# LapTopBoard.net
KiCad netlist of a schematic drawn in Altium Designer
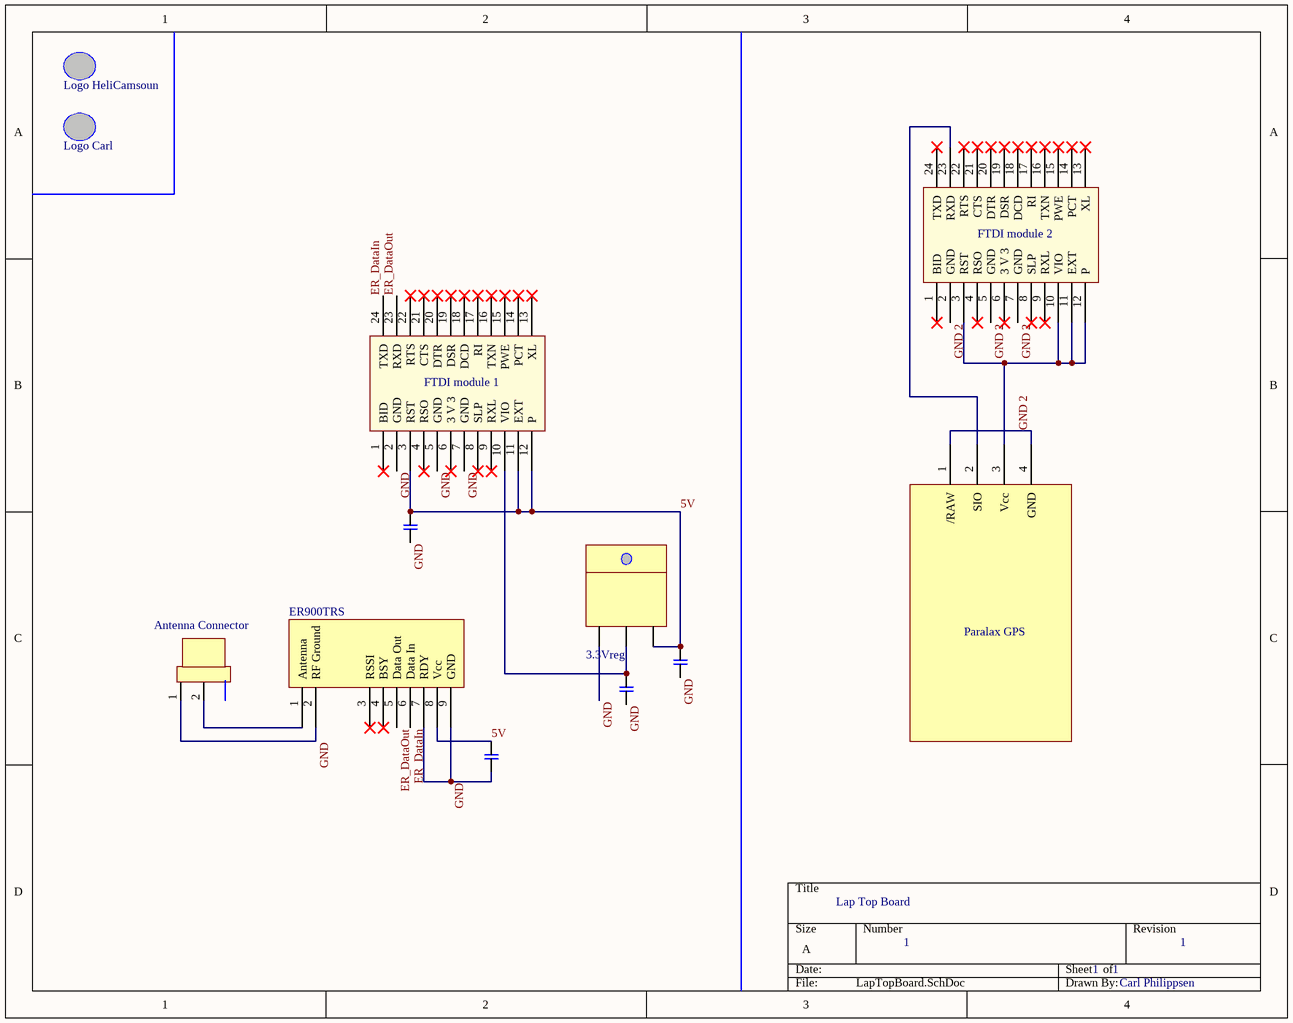
[diagram p0: LapTopBoard.SchDoc]

(export (version "E")
  (design (tool "Eeschema 10.0.6"))
  (components
    (comp (ref "2mmCap 1")
      (value "2mmCap")
      (footprint "2mmCap")
      (libsource (lib "MAX232Lib") (part "2mmCap"))
    )
    (comp (ref "2mmCap 2")
      (value "2mmCap")
      (footprint "2mmCap")
      (libsource (lib "MAX232Lib") (part "2mmCap"))
    )
    (comp (ref "2mmCap 3")
      (value "2mmCap")
      (footprint "2mmCap")
      (libsource (lib "MAX232Lib") (part "2mmCap"))
    )
    (comp (ref "2mmCap 4")
      (value "2mmCap")
      (footprint "2mmCap")
      (libsource (lib "MAX232Lib") (part "2mmCap"))
    )
    (comp (ref "3.3Vreg")
      (value "3.3Vreg")
      (footprint "3.3Vreg")
      (libsource (lib "MAX232Lib") (part "3.3Vreg"))
    )
    (comp (ref "Antenna Connector")
      (value "Antenna Connector")
      (footprint "Antenna Connector")
      (libsource (lib "MAX232Lib") (part "Antenna Connector"))
    )
    (comp (ref "ER900TRS")
      (value "Easy Radio 900MHz")
      (footprint "ER900TRS")
      (libsource (lib "MAX232Lib") (part "ER900TRS"))
    )
    (comp (ref "FTDI module 1")
      (value "FTDI module")
      (footprint "FTDI module")
      (libsource (lib "MAX232Lib") (part "FTDI module"))
    )
    (comp (ref "FTDI module 2")
      (value "FTDI module")
      (footprint "FTDI module")
      (libsource (lib "MAX232Lib") (part "FTDI module"))
    )
    (comp (ref "Logo Carl")
      (value "logo")
      (footprint "Carl Logo")
      (libsource (lib "MAX232Lib") (part "logo"))
    )
    (comp (ref "Logo HeliCamsoun")
      (value "logo")
      (footprint "HeliCamosun")
      (libsource (lib "MAX232Lib") (part "logo"))
    )
    (comp (ref "Paralax GPS")
      (value "Paralax GPS")
      (footprint "Paralax GPS")
      (libsource (lib "MAX232Lib") (part "Paralax GPS"))
    )
  )
  (nets
    (net (code "1") (name "/5V") (class "Default")
      (node (ref "2mmCap 1") (pin "1") (pinfunction "1_1") (pintype "passive"))
      (node (ref "2mmCap 3") (pin "1") (pinfunction "1_1") (pintype "passive"))
      (node (ref "2mmCap 4") (pin "1") (pinfunction "1_1") (pintype "passive"))
      (node (ref "3.3Vreg") (pin "3") (pinfunction "3_3") (pintype "passive"))
      (node (ref "ER900TRS") (pin "8") (pinfunction "Vcc_8") (pintype "passive"))
      (node (ref "FTDI module 1") (pin "11") (pinfunction "EXT_11") (pintype "passive"))
      (node (ref "FTDI module 1") (pin "12") (pinfunction "P_12") (pintype "passive"))
      (node (ref "FTDI module 1") (pin "3") (pinfunction "RST_3") (pintype "passive"))
    )
    (net (code "2") (name "/ER_DataIn") (class "Default")
      (node (ref "ER900TRS") (pin "6") (pinfunction "Data_In_6") (pintype "passive"))
      (node (ref "FTDI module 1") (pin "24") (pinfunction "TXD_24") (pintype "passive"))
    )
    (net (code "3") (name "/ER_DataOut") (class "Default")
      (node (ref "ER900TRS") (pin "5") (pinfunction "Data_Out_5") (pintype "passive"))
      (node (ref "FTDI module 1") (pin "23") (pinfunction "RXD_23") (pintype "passive"))
    )
    (net (code "4") (name "/GND") (class "Default")
      (node (ref "2mmCap 1") (pin "2") (pinfunction "2_2") (pintype "passive"))
      (node (ref "2mmCap 2") (pin "2") (pinfunction "2_2") (pintype "passive"))
      (node (ref "2mmCap 3") (pin "2") (pinfunction "2_2") (pintype "passive"))
      (node (ref "2mmCap 4") (pin "2") (pinfunction "2_2") (pintype "passive"))
      (node (ref "3.3Vreg") (pin "1") (pinfunction "1_1") (pintype "passive"))
      (node (ref "Antenna Connector") (pin "1") (pinfunction "1_1") (pintype "passive"))
      (node (ref "ER900TRS") (pin "2") (pinfunction "RF_Ground_2") (pintype "passive"))
      (node (ref "ER900TRS") (pin "7") (pinfunction "RDY_7") (pintype "passive"))
      (node (ref "ER900TRS") (pin "9") (pinfunction "GND_9") (pintype "passive"))
      (node (ref "FTDI module 1") (pin "2") (pinfunction "GND_2") (pintype "passive"))
      (node (ref "FTDI module 1") (pin "5") (pinfunction "GND_5") (pintype "passive"))
      (node (ref "FTDI module 1") (pin "7") (pinfunction "GND_7") (pintype "passive"))
    )
    (net (code "5") (name "/GND 2") (class "Default")
      (node (ref "FTDI module 2") (pin "2") (pinfunction "GND_2") (pintype "passive"))
      (node (ref "FTDI module 2") (pin "5") (pinfunction "GND_5") (pintype "passive"))
      (node (ref "FTDI module 2") (pin "7") (pinfunction "GND_7") (pintype "passive"))
      (node (ref "Paralax GPS") (pin "1") (pinfunction "/RAW_1") (pintype "passive"))
      (node (ref "Paralax GPS") (pin "4") (pinfunction "GND_4") (pintype "passive"))
    )
    (net (code "6") (name "Net-(ER900TRS-Antenna)") (class "Default")
      (node (ref "Antenna Connector") (pin "2") (pinfunction "2_2") (pintype "passive"))
      (node (ref "ER900TRS") (pin "1") (pinfunction "Antenna_1") (pintype "passive"))
    )
    (net (code "7") (name "Net-(FTDI module 1-VIO)") (class "Default")
      (node (ref "2mmCap 2") (pin "1") (pinfunction "1_1") (pintype "passive"))
      (node (ref "3.3Vreg") (pin "2") (pinfunction "2_2") (pintype "passive"))
      (node (ref "FTDI module 1") (pin "10") (pinfunction "VIO_10") (pintype "passive"))
    )
    (net (code "8") (name "Net-(FTDI module 2-EXT)") (class "Default")
      (node (ref "FTDI module 2") (pin "10") (pinfunction "VIO_10") (pintype "passive"))
      (node (ref "FTDI module 2") (pin "11") (pinfunction "EXT_11") (pintype "passive"))
      (node (ref "FTDI module 2") (pin "12") (pinfunction "P_12") (pintype "passive"))
      (node (ref "FTDI module 2") (pin "3") (pinfunction "RST_3") (pintype "passive"))
      (node (ref "Paralax GPS") (pin "3") (pinfunction "Vcc_3") (pintype "passive"))
    )
    (net (code "9") (name "Net-(FTDI module 2-RXD)") (class "Default")
      (node (ref "FTDI module 2") (pin "23") (pinfunction "RXD_23") (pintype "passive"))
      (node (ref "Paralax GPS") (pin "2") (pinfunction "SIO_2") (pintype "passive"))
    )
    (net (code "10") (name "unconnected-(ER900TRS-BSY-Pad4)") (class "Default")
      (node (ref "ER900TRS") (pin "4") (pinfunction "BSY_4") (pintype "passive+no_connect"))
    )
    (net (code "11") (name "unconnected-(ER900TRS-RSSI-Pad3)") (class "Default")
      (node (ref "ER900TRS") (pin "3") (pinfunction "RSSI_3") (pintype "passive+no_connect"))
    )
    (net (code "12") (name "unconnected-(FTDI module 1-3_V_3-Pad6)") (class "Default")
      (node (ref "FTDI module 1") (pin "6") (pinfunction "3_V_3_6") (pintype "passive+no_connect"))
    )
    (net (code "13") (name "unconnected-(FTDI module 1-BID-Pad1)") (class "Default")
      (node (ref "FTDI module 1") (pin "1") (pinfunction "BID_1") (pintype "passive+no_connect"))
    )
    (net (code "14") (name "unconnected-(FTDI module 1-CTS-Pad21)") (class "Default")
      (node (ref "FTDI module 1") (pin "21") (pinfunction "CTS_21") (pintype "passive+no_connect"))
    )
    (net (code "15") (name "unconnected-(FTDI module 1-DCD-Pad18)") (class "Default")
      (node (ref "FTDI module 1") (pin "18") (pinfunction "DCD_18") (pintype "passive+no_connect"))
    )
    (net (code "16") (name "unconnected-(FTDI module 1-DSR-Pad19)") (class "Default")
      (node (ref "FTDI module 1") (pin "19") (pinfunction "DSR_19") (pintype "passive+no_connect"))
    )
    (net (code "17") (name "unconnected-(FTDI module 1-DTR-Pad20)") (class "Default")
      (node (ref "FTDI module 1") (pin "20") (pinfunction "DTR_20") (pintype "passive+no_connect"))
    )
    (net (code "18") (name "unconnected-(FTDI module 1-PCT-Pad14)") (class "Default")
      (node (ref "FTDI module 1") (pin "14") (pinfunction "PCT_14") (pintype "passive+no_connect"))
    )
    (net (code "19") (name "unconnected-(FTDI module 1-PWE-Pad15)") (class "Default")
      (node (ref "FTDI module 1") (pin "15") (pinfunction "PWE_15") (pintype "passive+no_connect"))
    )
    (net (code "20") (name "unconnected-(FTDI module 1-RI-Pad17)") (class "Default")
      (node (ref "FTDI module 1") (pin "17") (pinfunction "RI_17") (pintype "passive+no_connect"))
    )
    (net (code "21") (name "unconnected-(FTDI module 1-RSO-Pad4)") (class "Default")
      (node (ref "FTDI module 1") (pin "4") (pinfunction "RSO_4") (pintype "passive+no_connect"))
    )
    (net (code "22") (name "unconnected-(FTDI module 1-RTS-Pad22)") (class "Default")
      (node (ref "FTDI module 1") (pin "22") (pinfunction "RTS_22") (pintype "passive+no_connect"))
    )
    (net (code "23") (name "unconnected-(FTDI module 1-RXL-Pad9)") (class "Default")
      (node (ref "FTDI module 1") (pin "9") (pinfunction "RXL_9") (pintype "passive+no_connect"))
    )
    (net (code "24") (name "unconnected-(FTDI module 1-SLP-Pad8)") (class "Default")
      (node (ref "FTDI module 1") (pin "8") (pinfunction "SLP_8") (pintype "passive+no_connect"))
    )
    (net (code "25") (name "unconnected-(FTDI module 1-TXN-Pad16)") (class "Default")
      (node (ref "FTDI module 1") (pin "16") (pinfunction "TXN_16") (pintype "passive+no_connect"))
    )
    (net (code "26") (name "unconnected-(FTDI module 1-XL-Pad13)") (class "Default")
      (node (ref "FTDI module 1") (pin "13") (pinfunction "XL_13") (pintype "passive+no_connect"))
    )
    (net (code "27") (name "unconnected-(FTDI module 2-3_V_3-Pad6)") (class "Default")
      (node (ref "FTDI module 2") (pin "6") (pinfunction "3_V_3_6") (pintype "passive+no_connect"))
    )
    (net (code "28") (name "unconnected-(FTDI module 2-BID-Pad1)") (class "Default")
      (node (ref "FTDI module 2") (pin "1") (pinfunction "BID_1") (pintype "passive+no_connect"))
    )
    (net (code "29") (name "unconnected-(FTDI module 2-CTS-Pad21)") (class "Default")
      (node (ref "FTDI module 2") (pin "21") (pinfunction "CTS_21") (pintype "passive+no_connect"))
    )
    (net (code "30") (name "unconnected-(FTDI module 2-DCD-Pad18)") (class "Default")
      (node (ref "FTDI module 2") (pin "18") (pinfunction "DCD_18") (pintype "passive+no_connect"))
    )
    (net (code "31") (name "unconnected-(FTDI module 2-DSR-Pad19)") (class "Default")
      (node (ref "FTDI module 2") (pin "19") (pinfunction "DSR_19") (pintype "passive+no_connect"))
    )
    (net (code "32") (name "unconnected-(FTDI module 2-DTR-Pad20)") (class "Default")
      (node (ref "FTDI module 2") (pin "20") (pinfunction "DTR_20") (pintype "passive+no_connect"))
    )
    (net (code "33") (name "unconnected-(FTDI module 2-PCT-Pad14)") (class "Default")
      (node (ref "FTDI module 2") (pin "14") (pinfunction "PCT_14") (pintype "passive+no_connect"))
    )
    (net (code "34") (name "unconnected-(FTDI module 2-PWE-Pad15)") (class "Default")
      (node (ref "FTDI module 2") (pin "15") (pinfunction "PWE_15") (pintype "passive+no_connect"))
    )
    (net (code "35") (name "unconnected-(FTDI module 2-RI-Pad17)") (class "Default")
      (node (ref "FTDI module 2") (pin "17") (pinfunction "RI_17") (pintype "passive+no_connect"))
    )
    (net (code "36") (name "unconnected-(FTDI module 2-RSO-Pad4)") (class "Default")
      (node (ref "FTDI module 2") (pin "4") (pinfunction "RSO_4") (pintype "passive+no_connect"))
    )
    (net (code "37") (name "unconnected-(FTDI module 2-RTS-Pad22)") (class "Default")
      (node (ref "FTDI module 2") (pin "22") (pinfunction "RTS_22") (pintype "passive+no_connect"))
    )
    (net (code "38") (name "unconnected-(FTDI module 2-RXL-Pad9)") (class "Default")
      (node (ref "FTDI module 2") (pin "9") (pinfunction "RXL_9") (pintype "passive+no_connect"))
    )
    (net (code "39") (name "unconnected-(FTDI module 2-SLP-Pad8)") (class "Default")
      (node (ref "FTDI module 2") (pin "8") (pinfunction "SLP_8") (pintype "passive+no_connect"))
    )
    (net (code "40") (name "unconnected-(FTDI module 2-TXD-Pad24)") (class "Default")
      (node (ref "FTDI module 2") (pin "24") (pinfunction "TXD_24") (pintype "passive+no_connect"))
    )
    (net (code "41") (name "unconnected-(FTDI module 2-TXN-Pad16)") (class "Default")
      (node (ref "FTDI module 2") (pin "16") (pinfunction "TXN_16") (pintype "passive+no_connect"))
    )
    (net (code "42") (name "unconnected-(FTDI module 2-XL-Pad13)") (class "Default")
      (node (ref "FTDI module 2") (pin "13") (pinfunction "XL_13") (pintype "passive+no_connect"))
    )
  )
)
